# ThermoCoupleCircuit.net
KiCad netlist of a schematic drawn in Altium Designer
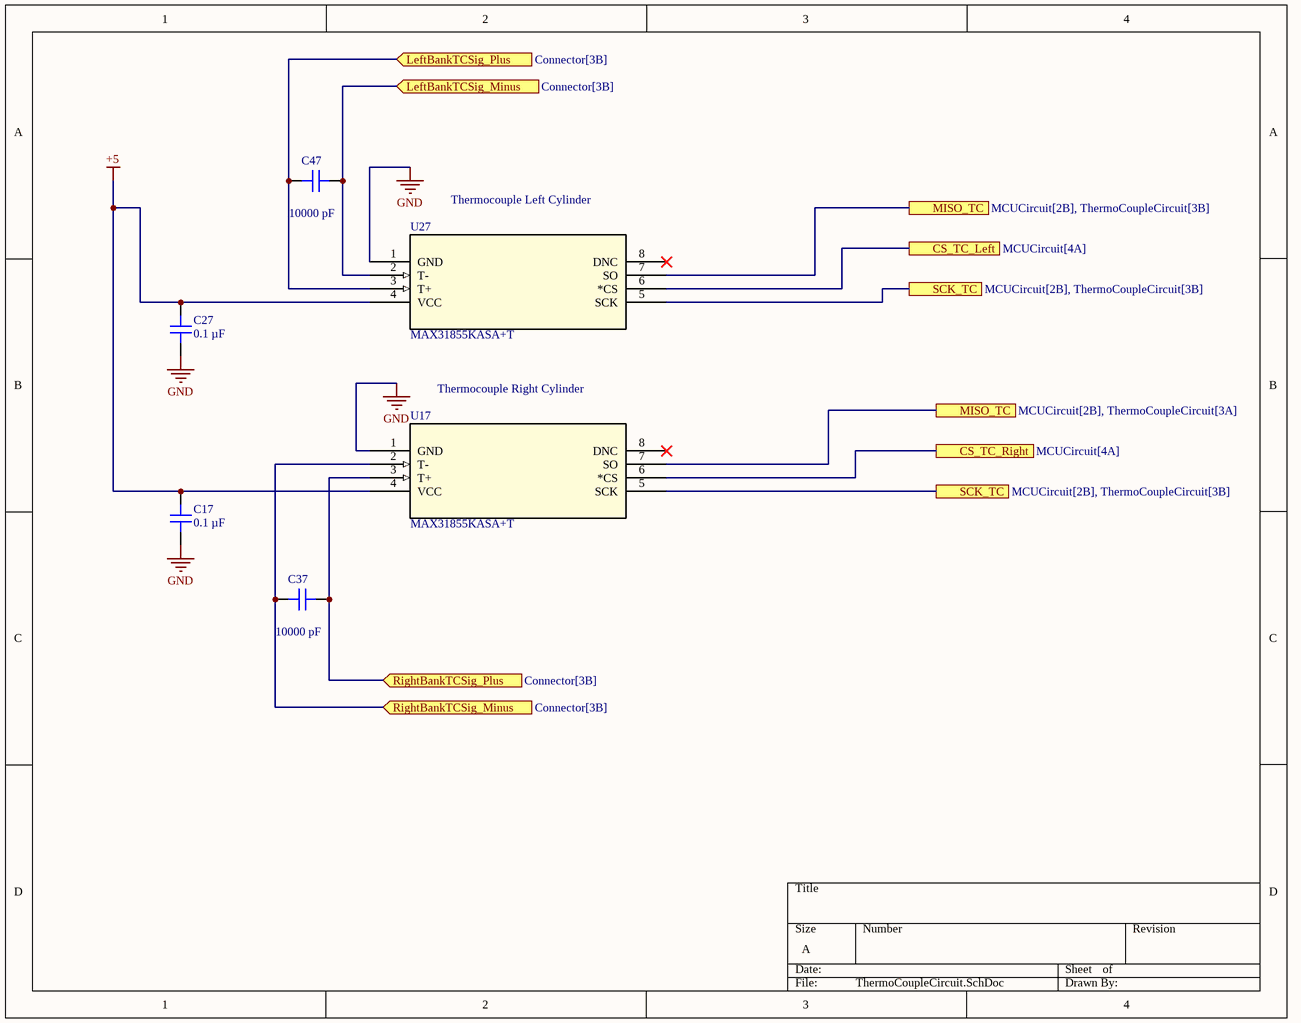
[diagram p0: ThermoCoupleCircuit.SchDoc]

(export (version "E")
  (design (tool "Eeschema 10.0.6"))
  (components
    (comp (ref "C17")
      (value "0.1 µF")
      (footprint "C0805")
      (description "CAP CER 0.1UF 16V X7R 0805")
      (fields
        (field (name "PART NUMBER") "0805B104K160CT")
        (field (name "MANUFACTURER") "Walsin Technology Corporation")
      )
      (libsource (lib "Celestial Altium Library - altium_library") (part "Capacitor"))
    )
    (comp (ref "C27")
      (value "0.1 µF")
      (footprint "C0805")
      (description "CAP CER 0.1UF 16V X7R 0805")
      (fields
        (field (name "PART NUMBER") "0805B104K160CT")
        (field (name "MANUFACTURER") "Walsin Technology Corporation")
      )
      (libsource (lib "Celestial Altium Library - altium_library") (part "Capacitor"))
    )
    (comp (ref "C37")
      (value "10000 pF")
      (footprint "C0805")
      (description "CAP CER 0805 10NF 16V X7R 10%")
      (fields (field (name "PART NUMBER") "C0805C103K4REC7800") (field (name "MANUFACTURER") "KEMET"))
      (libsource (lib "Celestial Altium Library - altium_library") (part "Capacitor"))
    )
    (comp (ref "C47")
      (value "10000 pF")
      (footprint "C0805")
      (description "CAP CER 0805 10NF 16V X7R 10%")
      (fields (field (name "PART NUMBER") "C0805C103K4REC7800") (field (name "MANUFACTURER") "KEMET"))
      (libsource (lib "Celestial Altium Library - altium_library") (part "Capacitor"))
    )
    (comp (ref "U17")
      (value "MAX31855KASA+T")
      (footprint "21-0041B_8_MXM")
      (description "No Description Available")
      (libsource (lib "MAX31855KASA&plus_T") (part "MAX31855KASA+T"))
    )
    (comp (ref "U27")
      (value "MAX31855KASA+T")
      (footprint "21-0041B_8_MXM")
      (description "No Description Available")
      (libsource (lib "MAX31855KASA&plus_T") (part "MAX31855KASA+T"))
    )
  )
  (nets
    (net (code "1") (name "+5") (class "Default")
      (node (ref "C17") (pin "2") (pinfunction "2_2") (pintype "passive"))
      (node (ref "C27") (pin "1") (pinfunction "1_1") (pintype "passive"))
      (node (ref "U17") (pin "4") (pinfunction "VCC_4") (pintype "power_in"))
      (node (ref "U27") (pin "4") (pinfunction "VCC_4") (pintype "power_in"))
    )
    (net (code "2") (name "/CS_TC_Left") (class "Default")
      (node (ref "U27") (pin "6") (pinfunction "*CS_6") (pintype "passive"))
    )
    (net (code "3") (name "/CS_TC_Right") (class "Default")
      (node (ref "U17") (pin "6") (pinfunction "*CS_6") (pintype "passive"))
    )
    (net (code "4") (name "/LeftBankTCSig_Minus") (class "Default")
      (node (ref "C47") (pin "2") (pinfunction "2_2") (pintype "passive"))
      (node (ref "U27") (pin "2") (pinfunction "T-_2") (pintype "input"))
    )
    (net (code "5") (name "/LeftBankTCSig_Plus") (class "Default")
      (node (ref "C47") (pin "1") (pinfunction "1_1") (pintype "passive"))
      (node (ref "U27") (pin "3") (pinfunction "T+_3") (pintype "input"))
    )
    (net (code "6") (name "/MISO_TC") (class "Default")
      (node (ref "U17") (pin "7") (pinfunction "SO_7") (pintype "passive"))
      (node (ref "U27") (pin "7") (pinfunction "SO_7") (pintype "passive"))
    )
    (net (code "7") (name "/RightBankTCSig_Minus") (class "Default")
      (node (ref "C37") (pin "1") (pinfunction "1_1") (pintype "passive"))
      (node (ref "U17") (pin "2") (pinfunction "T-_2") (pintype "input"))
    )
    (net (code "8") (name "/RightBankTCSig_Plus") (class "Default")
      (node (ref "C37") (pin "2") (pinfunction "2_2") (pintype "passive"))
      (node (ref "U17") (pin "3") (pinfunction "T+_3") (pintype "input"))
    )
    (net (code "9") (name "/SCK_TC") (class "Default")
      (node (ref "U17") (pin "5") (pinfunction "SCK_5") (pintype "passive"))
      (node (ref "U27") (pin "5") (pinfunction "SCK_5") (pintype "passive"))
    )
    (net (code "10") (name "GND") (class "Default")
      (node (ref "C17") (pin "1") (pinfunction "1_1") (pintype "passive"))
      (node (ref "C27") (pin "2") (pinfunction "2_2") (pintype "passive"))
      (node (ref "U17") (pin "1") (pinfunction "GND_1") (pintype "power_in"))
      (node (ref "U27") (pin "1") (pinfunction "GND_1") (pintype "power_in"))
    )
    (net (code "11") (name "unconnected-(U17-DNC-Pad8)") (class "Default")
      (node (ref "U17") (pin "8") (pinfunction "DNC_8") (pintype "passive+no_connect"))
    )
    (net (code "12") (name "unconnected-(U27-DNC-Pad8)") (class "Default")
      (node (ref "U27") (pin "8") (pinfunction "DNC_8") (pintype "passive+no_connect"))
    )
  )
)
